# SCH_Bai1.net
KiCad netlist of a schematic drawn in Altium Designer
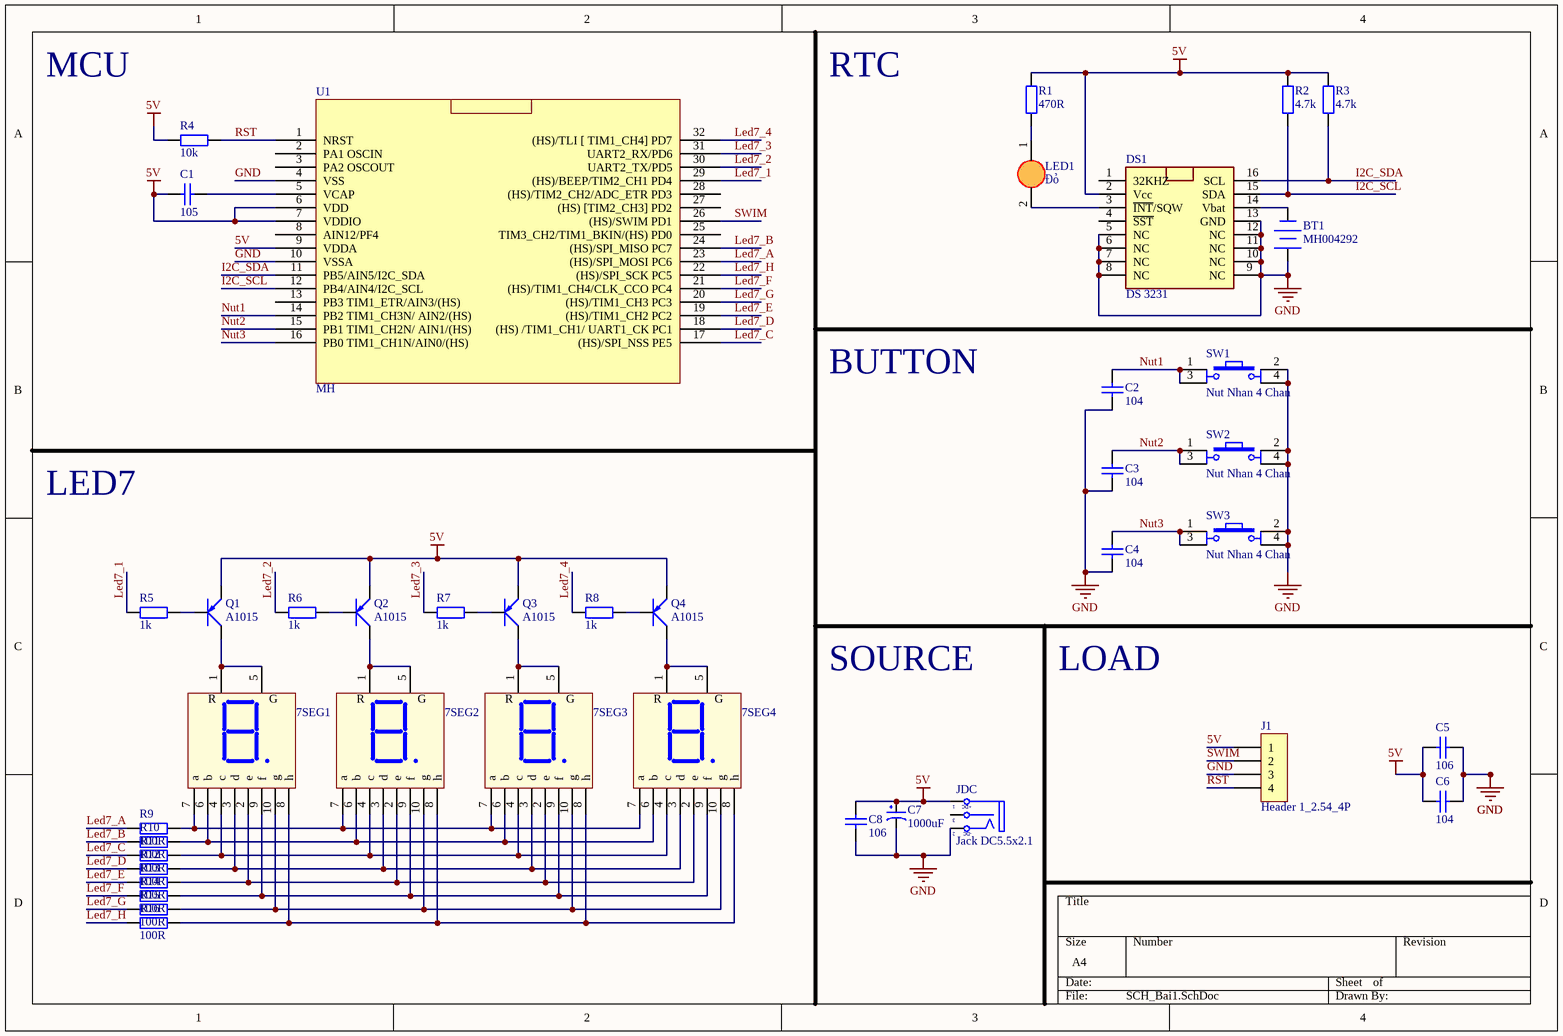
[diagram p0: SCH_Bai1.SchDoc]

(export (version "E")
  (design (tool "Eeschema 10.0.6"))
  (components
    (comp (ref "7SEG1")
      (value "Led 7 Thanh 2.3 Inch Anot")
      (footprint "LED 7 THANH X 1.8INCH")
      (description "Single 7 Seg Dipslay 29x41 mm")
      (libsource (lib "THU VIEN SCH") (part "LED 7SEG 2.3Inch"))
    )
    (comp (ref "7SEG2")
      (value "Led 7 Thanh 2.3 Inch Anot")
      (footprint "LED 7 THANH X 1.8INCH")
      (description "Single 7 Seg Dipslay 29x41 mm")
      (libsource (lib "THU VIEN SCH") (part "LED 7SEG 2.3Inch"))
    )
    (comp (ref "7SEG3")
      (value "Led 7 Thanh 2.3 Inch Anot")
      (footprint "LED 7 THANH X 1.8INCH")
      (description "Single 7 Seg Dipslay 29x41 mm")
      (libsource (lib "THU VIEN SCH") (part "LED 7SEG 2.3Inch"))
    )
    (comp (ref "7SEG4")
      (value "Led 7 Thanh 2.3 Inch Anot")
      (footprint "LED 7 THANH X 1.8INCH")
      (description "Single 7 Seg Dipslay 29x41 mm")
      (libsource (lib "THU VIEN SCH") (part "LED 7SEG 2.3Inch"))
    )
    (comp (ref "BT1")
      (value "MH004292")
      (footprint "DE PINCR1220")
      (description "Dán")
      (libsource (lib "THU VIEN SCH") (part "De Pin 3.3V"))
    )
    (comp (ref "C1")
      (value "105")
      (footprint "tu 0805")
      (description "Dán")
      (libsource (lib "THU VIEN SCH") (part "Tu 0805 105 50V 10%"))
    )
    (comp (ref "C2")
      (value "104")
      (footprint "tu 0805")
      (description "Dán")
      (libsource (lib "THU VIEN SCH") (part "Tu 0805 104 50V 10%"))
    )
    (comp (ref "C3")
      (value "104")
      (footprint "tu 0805")
      (description "Dán")
      (libsource (lib "THU VIEN SCH") (part "Tu 0805 104 50V 10%"))
    )
    (comp (ref "C4")
      (value "104")
      (footprint "tu 0805")
      (description "Dán")
      (libsource (lib "THU VIEN SCH") (part "Tu 0805 104 50V 10%"))
    )
    (comp (ref "C5")
      (value "106")
      (footprint "Tu 0805")
      (description "Dán")
      (libsource (lib "THU VIEN SCH") (part "Tu 0805 106 16V 10%"))
    )
    (comp (ref "C6")
      (value "104")
      (footprint "tu 0805")
      (description "Dán")
      (libsource (lib "THU VIEN SCH") (part "Tu 0805 104 50V 10%"))
    )
    (comp (ref "C7")
      (value "1000uF")
      (footprint "tu hoa 13mm")
      (description "Cắm")
      (libsource (lib "THU VIEN SCH") (part "Tu Hoa 1000uF 25V 13x21"))
    )
    (comp (ref "C8")
      (value "106")
      (footprint "Tu 0805")
      (description "Dán")
      (libsource (lib "THU VIEN SCH") (part "Tu 0805 106 16V 10%"))
    )
    (comp (ref "DS1")
      (value "DS 3231")
      (footprint "SOP16")
      (description "Dán")
      (libsource (lib "THU VIEN SCH") (part "DS 3231"))
    )
    (comp (ref "J1")
      (value "Header 1_2.54_4P")
      (footprint "Header_Duc Cong_4P 2.54")
      (description "Cắm")
      (libsource (lib "THU VIEN SCH") (part "Header 1_2.54_4P"))
    )
    (comp (ref "JDC")
      (value "Jack DC5.5x2.1")
      (footprint "DC-IN")
      (description "Cắm")
      (libsource (lib "THU VIEN SCH") (part "Jac_DC"))
    )
    (comp (ref "LED1")
      (value "Đỏ")
      (footprint "led 0805")
      (description "Dán")
      (libsource (lib "THU VIEN SCH") (part "LED 0805"))
    )
    (comp (ref "Q1")
      (value "A1015")
      (footprint "SOT23")
      (description "Dán")
      (libsource (lib "THU VIEN SCH") (part "A1015"))
    )
    (comp (ref "Q2")
      (value "A1015")
      (footprint "SOT23")
      (description "Dán")
      (libsource (lib "THU VIEN SCH") (part "A1015"))
    )
    (comp (ref "Q3")
      (value "A1015")
      (footprint "SOT23")
      (description "Dán")
      (libsource (lib "THU VIEN SCH") (part "A1015"))
    )
    (comp (ref "Q4")
      (value "A1015")
      (footprint "SOT23")
      (description "Dán")
      (libsource (lib "THU VIEN SCH") (part "A1015"))
    )
    (comp (ref "R1")
      (value "470R")
      (footprint "Tro SMD 0805")
      (description "Dán")
      (libsource (lib "THU VIEN SCH") (part "Tro 0805 5% 470R"))
    )
    (comp (ref "R2")
      (value "4.7k")
      (footprint "tro smd 0805")
      (description "Dán")
      (libsource (lib "THU VIEN SCH") (part "Tro 0805 5% 4.7k"))
    )
    (comp (ref "R3")
      (value "4.7k")
      (footprint "tro smd 0805")
      (description "Dán")
      (libsource (lib "THU VIEN SCH") (part "Tro 0805 5% 4.7k"))
    )
    (comp (ref "R4")
      (value "10k")
      (footprint "tro smd 0805")
      (description "Dán")
      (libsource (lib "THU VIEN SCH") (part "Tro 0805 1% 10k"))
    )
    (comp (ref "R5")
      (value "1k")
      (footprint "tro smd 0805")
      (description "Dán")
      (libsource (lib "THU VIEN SCH") (part "Tro 0805 5% 1k"))
    )
    (comp (ref "R6")
      (value "1k")
      (footprint "tro smd 0805")
      (description "Dán")
      (libsource (lib "THU VIEN SCH") (part "Tro 0805 1% 1k"))
    )
    (comp (ref "R7")
      (value "1k")
      (footprint "tro smd 0805")
      (description "Dán")
      (libsource (lib "THU VIEN SCH") (part "Tro 0805 1% 1k"))
    )
    (comp (ref "R8")
      (value "1k")
      (footprint "tro smd 0805")
      (description "Dán")
      (libsource (lib "THU VIEN SCH") (part "Tro 0805 1% 1k"))
    )
    (comp (ref "R9")
      (value "100R")
      (footprint "tro smd 0805")
      (description "Dán")
      (libsource (lib "THU VIEN SCH") (part "Tro 0805 5% 100R"))
    )
    (comp (ref "R10")
      (value "100R")
      (footprint "tro smd 0805")
      (description "Dán")
      (libsource (lib "THU VIEN SCH") (part "Tro 0805 5% 100R"))
    )
    (comp (ref "R11")
      (value "100R")
      (footprint "tro smd 0805")
      (description "Dán")
      (libsource (lib "THU VIEN SCH") (part "Tro 0805 5% 100R"))
    )
    (comp (ref "R12")
      (value "100R")
      (footprint "tro smd 0805")
      (description "Dán")
      (libsource (lib "THU VIEN SCH") (part "Tro 0805 5% 100R"))
    )
    (comp (ref "R13")
      (value "100R")
      (footprint "tro smd 0805")
      (description "Dán")
      (libsource (lib "THU VIEN SCH") (part "Tro 0805 5% 100R"))
    )
    (comp (ref "R14")
      (value "100R")
      (footprint "tro smd 0805")
      (description "Dán")
      (libsource (lib "THU VIEN SCH") (part "Tro 0805 5% 100R"))
    )
    (comp (ref "R15")
      (value "100R")
      (footprint "tro smd 0805")
      (description "Dán")
      (libsource (lib "THU VIEN SCH") (part "Tro 0805 5% 100R"))
    )
    (comp (ref "R16")
      (value "100R")
      (footprint "tro smd 0805")
      (description "Dán")
      (libsource (lib "THU VIEN SCH") (part "Tro 0805 5% 100R"))
    )
    (comp (ref "SW1")
      (value "Nut Nhan 4 Chan")
      (footprint "SW4")
      (description "Cắm")
      (libsource (lib "THU VIEN SCH") (part "Nut Nhan 4 Chan"))
    )
    (comp (ref "SW2")
      (value "Nut Nhan 4 Chan")
      (footprint "SW4")
      (description "Cắm")
      (libsource (lib "THU VIEN SCH") (part "Nut Nhan 4 Chan"))
    )
    (comp (ref "SW3")
      (value "Nut Nhan 4 Chan")
      (footprint "SW4")
      (description "Cắm")
      (libsource (lib "THU VIEN SCH") (part "Nut Nhan 4 Chan"))
    )
    (comp (ref "U1")
      (value "MH")
      (footprint "32A_M")
      (description "Dán")
      (libsource (lib "THU VIEN SCH") (part "STM8S005K6T6C"))
    )
  )
  (nets
    (net (code "1") (name "/I2C_SCL") (class "Default")
      (node (ref "DS1") (pin "15") (pinfunction "SDA_15") (pintype "passive"))
      (node (ref "R2") (pin "1") (pinfunction "1_1") (pintype "passive"))
      (node (ref "U1") (pin "12") (pinfunction "PB4/AIN4/I2C_SCL_12") (pintype "passive"))
    )
    (net (code "2") (name "/I2C_SDA") (class "Default")
      (node (ref "DS1") (pin "16") (pinfunction "SCL_16") (pintype "passive"))
      (node (ref "R3") (pin "1") (pinfunction "1_1") (pintype "passive"))
      (node (ref "U1") (pin "11") (pinfunction "PB5/AIN5/I2C_SDA_11") (pintype "passive"))
    )
    (net (code "3") (name "/Led7_1") (class "Default")
      (node (ref "R5") (pin "1") (pinfunction "1_1") (pintype "passive"))
      (node (ref "U1") (pin "29") (pinfunction "(HS)/BEEP/TIM2_CH1_PD4_29") (pintype "passive"))
    )
    (net (code "4") (name "/Led7_2") (class "Default")
      (node (ref "R6") (pin "1") (pinfunction "1_1") (pintype "passive"))
      (node (ref "U1") (pin "30") (pinfunction "UART2_TX/PD5_30") (pintype "passive"))
    )
    (net (code "5") (name "/Led7_3") (class "Default")
      (node (ref "R7") (pin "1") (pinfunction "1_1") (pintype "passive"))
      (node (ref "U1") (pin "31") (pinfunction "UART2_RX/PD6_31") (pintype "passive"))
    )
    (net (code "6") (name "/Led7_4") (class "Default")
      (node (ref "R8") (pin "1") (pinfunction "1_1") (pintype "passive"))
      (node (ref "U1") (pin "32") (pinfunction "(HS)/TLI_[_TIM1_CH4]_PD7_32") (pintype "passive"))
    )
    (net (code "7") (name "/Led7_A") (class "Default")
      (node (ref "R9") (pin "1") (pinfunction "1_1") (pintype "passive"))
      (node (ref "U1") (pin "23") (pinfunction "(HS)/SPI_MOSI_PC6_23") (pintype "passive"))
    )
    (net (code "8") (name "/Led7_B") (class "Default")
      (node (ref "R10") (pin "1") (pinfunction "1_1") (pintype "passive"))
      (node (ref "U1") (pin "24") (pinfunction "(HS)/SPI_MISO_PC7_24") (pintype "passive"))
    )
    (net (code "9") (name "/Led7_C") (class "Default")
      (node (ref "R11") (pin "1") (pinfunction "1_1") (pintype "passive"))
      (node (ref "U1") (pin "17") (pinfunction "(HS)/SPI_NSS_PE5_17") (pintype "passive"))
    )
    (net (code "10") (name "/Led7_D") (class "Default")
      (node (ref "R12") (pin "1") (pinfunction "1_1") (pintype "passive"))
      (node (ref "U1") (pin "18") (pinfunction "(HS)_/TIM1_CH1/_UART1_CK_PC1_18") (pintype "passive"))
    )
    (net (code "11") (name "/Led7_E") (class "Default")
      (node (ref "R13") (pin "1") (pinfunction "1_1") (pintype "passive"))
      (node (ref "U1") (pin "19") (pinfunction "(HS)/TIM1_CH2_PC2_19") (pintype "passive"))
    )
    (net (code "12") (name "/Led7_F") (class "Default")
      (node (ref "R14") (pin "1") (pinfunction "1_1") (pintype "passive"))
      (node (ref "U1") (pin "21") (pinfunction "(HS)/TIM1_CH4/CLK_CCO_PC4_21") (pintype "passive"))
    )
    (net (code "13") (name "/Led7_G") (class "Default")
      (node (ref "R15") (pin "1") (pinfunction "1_1") (pintype "passive"))
      (node (ref "U1") (pin "20") (pinfunction "(HS)/TIM1_CH3_PC3_20") (pintype "passive"))
    )
    (net (code "14") (name "/Led7_H") (class "Default")
      (node (ref "R16") (pin "1") (pinfunction "1_1") (pintype "passive"))
      (node (ref "U1") (pin "22") (pinfunction "(HS)/SPI_SCK_PC5_22") (pintype "passive"))
    )
    (net (code "15") (name "/Nut1") (class "Default")
      (node (ref "C2") (pin "1") (pinfunction "1_1") (pintype "passive"))
      (node (ref "SW1") (pin "1") (pintype "passive"))
      (node (ref "SW1") (pin "3") (pintype "passive"))
      (node (ref "U1") (pin "14") (pinfunction "PB2_TIM1_CH3N/_AIN2/(HS)_14") (pintype "passive"))
    )
    (net (code "16") (name "/Nut2") (class "Default")
      (node (ref "C3") (pin "1") (pinfunction "1_1") (pintype "passive"))
      (node (ref "SW2") (pin "1") (pintype "passive"))
      (node (ref "SW2") (pin "3") (pintype "passive"))
      (node (ref "U1") (pin "15") (pinfunction "PB1_TIM1_CH2N/_AIN1/(HS)_15") (pintype "passive"))
    )
    (net (code "17") (name "/Nut3") (class "Default")
      (node (ref "C4") (pin "1") (pinfunction "1_1") (pintype "passive"))
      (node (ref "SW3") (pin "1") (pintype "passive"))
      (node (ref "SW3") (pin "3") (pintype "passive"))
      (node (ref "U1") (pin "16") (pinfunction "PB0_TIM1_CH1N/AIN0/(HS)_16") (pintype "passive"))
    )
    (net (code "18") (name "/RST") (class "Default")
      (node (ref "J1") (pin "4") (pinfunction "4_4") (pintype "passive"))
      (node (ref "R4") (pin "2") (pinfunction "2_2") (pintype "passive"))
      (node (ref "U1") (pin "1") (pinfunction "NRST_1") (pintype "passive"))
    )
    (net (code "19") (name "/SWIM") (class "Default")
      (node (ref "J1") (pin "2") (pinfunction "2_2") (pintype "passive"))
      (node (ref "U1") (pin "26") (pinfunction "(HS)/SWIM_PD1_26") (pintype "passive"))
    )
    (net (code "20") (name "5V") (class "Default")
      (node (ref "C1") (pin "2") (pinfunction "2_2") (pintype "passive"))
      (node (ref "C5") (pin "2") (pinfunction "2_2") (pintype "passive"))
      (node (ref "C6") (pin "2") (pinfunction "2_2") (pintype "passive"))
      (node (ref "C7") (pin "1") (pinfunction "1_1") (pintype "passive"))
      (node (ref "C8") (pin "1") (pinfunction "1_1") (pintype "passive"))
      (node (ref "DS1") (pin "2") (pinfunction "Vcc_2") (pintype "passive"))
      (node (ref "J1") (pin "1") (pinfunction "1_1") (pintype "passive"))
      (node (ref "JDC") (pin "1") (pinfunction "T_1") (pintype "passive"))
      (node (ref "Q1") (pin "3") (pinfunction "E_3") (pintype "passive"))
      (node (ref "Q2") (pin "3") (pinfunction "E_3") (pintype "passive"))
      (node (ref "Q3") (pin "3") (pinfunction "E_3") (pintype "passive"))
      (node (ref "Q4") (pin "3") (pinfunction "E_3") (pintype "passive"))
      (node (ref "R1") (pin "1") (pinfunction "1_1") (pintype "passive"))
      (node (ref "R2") (pin "2") (pinfunction "2_2") (pintype "passive"))
      (node (ref "R3") (pin "2") (pinfunction "2_2") (pintype "passive"))
      (node (ref "R4") (pin "1") (pinfunction "1_1") (pintype "passive"))
      (node (ref "U1") (pin "6") (pinfunction "VDD_6") (pintype "passive"))
      (node (ref "U1") (pin "7") (pinfunction "VDDIO_7") (pintype "passive"))
      (node (ref "U1") (pin "9") (pinfunction "VDDA_9") (pintype "passive"))
    )
    (net (code "21") (name "GND") (class "Default")
      (node (ref "BT1") (pin "1") (pinfunction "+_1") (pintype "passive"))
      (node (ref "C2") (pin "2") (pinfunction "2_2") (pintype "passive"))
      (node (ref "C3") (pin "2") (pinfunction "2_2") (pintype "passive"))
      (node (ref "C4") (pin "2") (pinfunction "2_2") (pintype "passive"))
      (node (ref "C5") (pin "1") (pinfunction "1_1") (pintype "passive"))
      (node (ref "C6") (pin "1") (pinfunction "1_1") (pintype "passive"))
      (node (ref "C7") (pin "2") (pinfunction "2_2") (pintype "passive"))
      (node (ref "C8") (pin "2") (pinfunction "2_2") (pintype "passive"))
      (node (ref "DS1") (pin "10") (pinfunction "NC_10") (pintype "passive"))
      (node (ref "DS1") (pin "11") (pinfunction "NC_11") (pintype "passive"))
      (node (ref "DS1") (pin "12") (pinfunction "NC_12") (pintype "passive"))
      (node (ref "DS1") (pin "13") (pinfunction "GND_13") (pintype "passive"))
      (node (ref "DS1") (pin "5") (pinfunction "NC_5") (pintype "passive"))
      (node (ref "DS1") (pin "6") (pinfunction "NC_6") (pintype "passive"))
      (node (ref "DS1") (pin "7") (pinfunction "NC_7") (pintype "passive"))
      (node (ref "DS1") (pin "8") (pinfunction "NC_8") (pintype "passive"))
      (node (ref "DS1") (pin "9") (pinfunction "NC_9") (pintype "passive"))
      (node (ref "J1") (pin "3") (pinfunction "3_3") (pintype "passive"))
      (node (ref "JDC") (pin "2") (pinfunction "TN_2") (pintype "passive"))
      (node (ref "SW1") (pin "2") (pintype "passive"))
      (node (ref "SW1") (pin "4") (pintype "passive"))
      (node (ref "SW2") (pin "2") (pintype "passive"))
      (node (ref "SW2") (pin "4") (pintype "passive"))
      (node (ref "SW3") (pin "2") (pintype "passive"))
      (node (ref "SW3") (pin "4") (pintype "passive"))
      (node (ref "U1") (pin "10") (pinfunction "VSSA_10") (pintype "passive"))
      (node (ref "U1") (pin "4") (pinfunction "VSS_4") (pintype "passive"))
    )
    (net (code "22") (name "Net-(7SEG1-COM)") (class "Default")
      (node (ref "7SEG1") (pin "1") (pinfunction "R_1") (pintype "passive"))
      (node (ref "7SEG1") (pin "5") (pinfunction "COM_5") (pintype "passive"))
      (node (ref "Q1") (pin "2") (pinfunction "C_2") (pintype "passive"))
    )
    (net (code "23") (name "Net-(7SEG1-a)") (class "Default")
      (node (ref "7SEG1") (pin "7") (pinfunction "a_7") (pintype "passive"))
      (node (ref "7SEG2") (pin "7") (pinfunction "a_7") (pintype "passive"))
      (node (ref "7SEG3") (pin "7") (pinfunction "a_7") (pintype "passive"))
      (node (ref "7SEG4") (pin "7") (pinfunction "a_7") (pintype "passive"))
      (node (ref "R9") (pin "2") (pinfunction "2_2") (pintype "passive"))
    )
    (net (code "24") (name "Net-(7SEG1-b)") (class "Default")
      (node (ref "7SEG1") (pin "6") (pinfunction "b_6") (pintype "passive"))
      (node (ref "7SEG2") (pin "6") (pinfunction "b_6") (pintype "passive"))
      (node (ref "7SEG3") (pin "6") (pinfunction "b_6") (pintype "passive"))
      (node (ref "7SEG4") (pin "6") (pinfunction "b_6") (pintype "passive"))
      (node (ref "R10") (pin "2") (pinfunction "2_2") (pintype "passive"))
    )
    (net (code "25") (name "Net-(7SEG1-c)") (class "Default")
      (node (ref "7SEG1") (pin "4") (pinfunction "c_4") (pintype "passive"))
      (node (ref "7SEG2") (pin "4") (pinfunction "c_4") (pintype "passive"))
      (node (ref "7SEG3") (pin "4") (pinfunction "c_4") (pintype "passive"))
      (node (ref "7SEG4") (pin "4") (pinfunction "c_4") (pintype "passive"))
      (node (ref "R11") (pin "2") (pinfunction "2_2") (pintype "passive"))
    )
    (net (code "26") (name "Net-(7SEG1-d)") (class "Default")
      (node (ref "7SEG1") (pin "3") (pinfunction "d_3") (pintype "passive"))
      (node (ref "7SEG2") (pin "3") (pinfunction "d_3") (pintype "passive"))
      (node (ref "7SEG3") (pin "3") (pinfunction "d_3") (pintype "passive"))
      (node (ref "7SEG4") (pin "3") (pinfunction "d_3") (pintype "passive"))
      (node (ref "R12") (pin "2") (pinfunction "2_2") (pintype "passive"))
    )
    (net (code "27") (name "Net-(7SEG1-e)") (class "Default")
      (node (ref "7SEG1") (pin "2") (pinfunction "e_2") (pintype "passive"))
      (node (ref "7SEG2") (pin "2") (pinfunction "e_2") (pintype "passive"))
      (node (ref "7SEG3") (pin "2") (pinfunction "e_2") (pintype "passive"))
      (node (ref "7SEG4") (pin "2") (pinfunction "e_2") (pintype "passive"))
      (node (ref "R13") (pin "2") (pinfunction "2_2") (pintype "passive"))
    )
    (net (code "28") (name "Net-(7SEG1-f)") (class "Default")
      (node (ref "7SEG1") (pin "9") (pinfunction "f_9") (pintype "passive"))
      (node (ref "7SEG2") (pin "9") (pinfunction "f_9") (pintype "passive"))
      (node (ref "7SEG3") (pin "9") (pinfunction "f_9") (pintype "passive"))
      (node (ref "7SEG4") (pin "9") (pinfunction "f_9") (pintype "passive"))
      (node (ref "R14") (pin "2") (pinfunction "2_2") (pintype "passive"))
    )
    (net (code "29") (name "Net-(7SEG1-g)") (class "Default")
      (node (ref "7SEG1") (pin "10") (pinfunction "g_10") (pintype "passive"))
      (node (ref "7SEG2") (pin "10") (pinfunction "g_10") (pintype "passive"))
      (node (ref "7SEG3") (pin "10") (pinfunction "g_10") (pintype "passive"))
      (node (ref "7SEG4") (pin "10") (pinfunction "g_10") (pintype "passive"))
      (node (ref "R15") (pin "2") (pinfunction "2_2") (pintype "passive"))
    )
    (net (code "30") (name "Net-(7SEG1-h)") (class "Default")
      (node (ref "7SEG1") (pin "8") (pinfunction "h_8") (pintype "passive"))
      (node (ref "7SEG2") (pin "8") (pinfunction "h_8") (pintype "passive"))
      (node (ref "7SEG3") (pin "8") (pinfunction "h_8") (pintype "passive"))
      (node (ref "7SEG4") (pin "8") (pinfunction "h_8") (pintype "passive"))
      (node (ref "R16") (pin "2") (pinfunction "2_2") (pintype "passive"))
    )
    (net (code "31") (name "Net-(7SEG2-COM)") (class "Default")
      (node (ref "7SEG2") (pin "1") (pinfunction "R_1") (pintype "passive"))
      (node (ref "7SEG2") (pin "5") (pinfunction "COM_5") (pintype "passive"))
      (node (ref "Q2") (pin "2") (pinfunction "C_2") (pintype "passive"))
    )
    (net (code "32") (name "Net-(7SEG3-COM)") (class "Default")
      (node (ref "7SEG3") (pin "1") (pinfunction "R_1") (pintype "passive"))
      (node (ref "7SEG3") (pin "5") (pinfunction "COM_5") (pintype "passive"))
      (node (ref "Q3") (pin "2") (pinfunction "C_2") (pintype "passive"))
    )
    (net (code "33") (name "Net-(7SEG4-COM)") (class "Default")
      (node (ref "7SEG4") (pin "1") (pinfunction "R_1") (pintype "passive"))
      (node (ref "7SEG4") (pin "5") (pinfunction "COM_5") (pintype "passive"))
      (node (ref "Q4") (pin "2") (pinfunction "C_2") (pintype "passive"))
    )
    (net (code "34") (name "Net-(BT1--)") (class "Default")
      (node (ref "BT1") (pin "2") (pinfunction "-_2") (pintype "passive"))
      (node (ref "DS1") (pin "14") (pinfunction "Vbat_14") (pintype "passive"))
    )
    (net (code "35") (name "Net-(DS1-~{INT}{slash}SQW)") (class "Default")
      (node (ref "DS1") (pin "3") (pinfunction "~{INT}/SQW_3") (pintype "passive"))
      (node (ref "LED1") (pin "2") (pinfunction "K_2") (pintype "passive"))
    )
    (net (code "36") (name "Net-(LED1-A)") (class "Default")
      (node (ref "LED1") (pin "1") (pinfunction "A_1") (pintype "passive"))
      (node (ref "R1") (pin "2") (pinfunction "2_2") (pintype "passive"))
    )
    (net (code "37") (name "Net-(Q1-B)") (class "Default")
      (node (ref "Q1") (pin "1") (pinfunction "B_1") (pintype "passive"))
      (node (ref "R5") (pin "2") (pinfunction "2_2") (pintype "passive"))
    )
    (net (code "38") (name "Net-(Q2-B)") (class "Default")
      (node (ref "Q2") (pin "1") (pinfunction "B_1") (pintype "passive"))
      (node (ref "R6") (pin "2") (pinfunction "2_2") (pintype "passive"))
    )
    (net (code "39") (name "Net-(Q3-B)") (class "Default")
      (node (ref "Q3") (pin "1") (pinfunction "B_1") (pintype "passive"))
      (node (ref "R7") (pin "2") (pinfunction "2_2") (pintype "passive"))
    )
    (net (code "40") (name "Net-(Q4-B)") (class "Default")
      (node (ref "Q4") (pin "1") (pinfunction "B_1") (pintype "passive"))
      (node (ref "R8") (pin "2") (pinfunction "2_2") (pintype "passive"))
    )
    (net (code "41") (name "Net-(U1-VCAP)") (class "Default")
      (node (ref "C1") (pin "1") (pinfunction "1_1") (pintype "passive"))
      (node (ref "U1") (pin "5") (pinfunction "VCAP_5") (pintype "passive"))
    )
    (net (code "42") (name "unconnected-(DS1-32KHZ-Pad1)") (class "Default")
      (node (ref "DS1") (pin "1") (pinfunction "32KHZ_1") (pintype "passive"))
    )
    (net (code "43") (name "unconnected-(DS1-~{SST}-Pad4)") (class "Default")
      (node (ref "DS1") (pin "4") (pinfunction "~{SST}_4") (pintype "passive"))
    )
    (net (code "44") (name "unconnected-(JDC-S-Pad3)") (class "Default")
      (node (ref "JDC") (pin "3") (pinfunction "S_3") (pintype "power_in"))
    )
    (net (code "45") (name "unconnected-(U1-(HS)_[TIM2_CH3]_PD2-Pad27)") (class "Default")
      (node (ref "U1") (pin "27") (pinfunction "(HS)_[TIM2_CH3]_PD2_27") (pintype "passive"))
    )
    (net (code "46") (name "unconnected-(U1-(HS){slash}TIM2_CH2{slash}ADC_ETR_PD3-Pad28)") (class "Default")
      (node (ref "U1") (pin "28") (pinfunction "(HS)/TIM2_CH2/ADC_ETR_PD3_28") (pintype "passive"))
    )
    (net (code "47") (name "unconnected-(U1-AIN12{slash}PF4-Pad8)") (class "Default")
      (node (ref "U1") (pin "8") (pinfunction "AIN12/PF4_8") (pintype "passive"))
    )
    (net (code "48") (name "unconnected-(U1-PA1_OSCIN-Pad2)") (class "Default")
      (node (ref "U1") (pin "2") (pinfunction "PA1_OSCIN_2") (pintype "passive"))
    )
    (net (code "49") (name "unconnected-(U1-PA2_OSCOUT-Pad3)") (class "Default")
      (node (ref "U1") (pin "3") (pinfunction "PA2_OSCOUT_3") (pintype "passive"))
    )
    (net (code "50") (name "unconnected-(U1-PB3_TIM1_ETR{slash}AIN3{slash}(HS)-Pad13)") (class "Default")
      (node (ref "U1") (pin "13") (pinfunction "PB3_TIM1_ETR/AIN3/(HS)_13") (pintype "passive"))
    )
    (net (code "51") (name "unconnected-(U1-TIM3_CH2{slash}TIM1_BKIN{slash}(HS)_PD0-Pad25)") (class "Default")
      (node (ref "U1") (pin "25") (pinfunction "TIM3_CH2/TIM1_BKIN/(HS)_PD0_25") (pintype "passive"))
    )
  )
)
